# Sheet2.net
KiCad netlist of a schematic drawn in Altium Designer
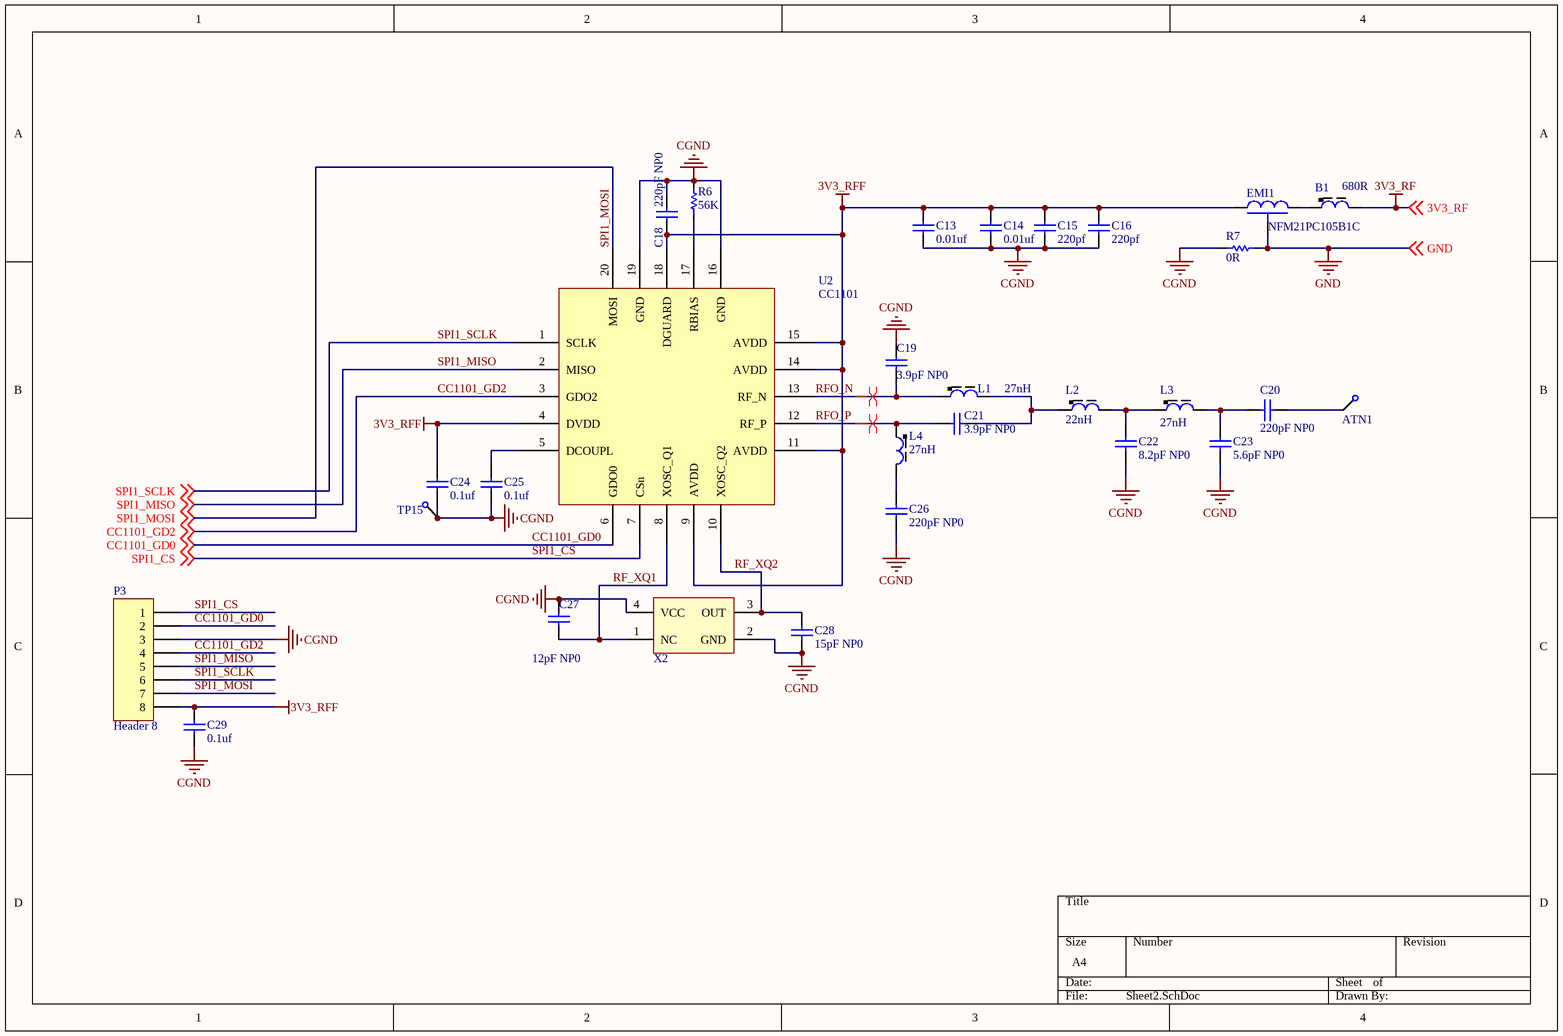
[diagram p0: Sheet2.SchDoc]

(export (version "E")
  (design (tool "Eeschema 10.0.6"))
  (components
    (comp (ref "ATN1")
      (value "TestPoint")
      (footprint "TP")
      (description "一个测试点")
      (libsource (lib "liber") (part "TestPoint"))
    )
    (comp (ref "B1") (value "680R") (footprint "L0603") (libsource (lib "liber") (part "L")))
    (comp (ref "C13")
      (value "0.01uf")
      (footprint "C0603")
      (description "Capacitor")
      (libsource (lib "liber") (part "Cap"))
    )
    (comp (ref "C14")
      (value "0.01uf")
      (footprint "C0603")
      (description "Capacitor")
      (libsource (lib "liber") (part "Cap"))
    )
    (comp (ref "C15")
      (value "220pf")
      (footprint "C0603")
      (description "Capacitor")
      (libsource (lib "liber") (part "Cap"))
    )
    (comp (ref "C16")
      (value "220pf")
      (footprint "C0603")
      (description "Capacitor")
      (libsource (lib "liber") (part "Cap"))
    )
    (comp (ref "C18")
      (value "220pF NP0")
      (footprint "C0603")
      (description "Capacitor")
      (libsource (lib "liber") (part "Cap"))
    )
    (comp (ref "C19")
      (value "3.9pF NP0")
      (footprint "C0603")
      (description "Capacitor")
      (libsource (lib "liber") (part "Cap"))
    )
    (comp (ref "C20")
      (value "220pF NP0")
      (footprint "C0603")
      (description "Capacitor")
      (libsource (lib "liber") (part "Cap"))
    )
    (comp (ref "C21")
      (value "3.9pF NP0")
      (footprint "C0603")
      (description "Capacitor")
      (libsource (lib "liber") (part "Cap"))
    )
    (comp (ref "C22")
      (value "8.2pF NP0")
      (footprint "C0603")
      (description "Capacitor")
      (libsource (lib "liber") (part "Cap"))
    )
    (comp (ref "C23")
      (value "5.6pF NP0")
      (footprint "C0603")
      (description "Capacitor")
      (libsource (lib "liber") (part "Cap"))
    )
    (comp (ref "C24")
      (value "0.1uf")
      (footprint "C0603")
      (description "Capacitor")
      (libsource (lib "liber") (part "Cap"))
    )
    (comp (ref "C25")
      (value "0.1uf")
      (footprint "C0603")
      (description "Capacitor")
      (libsource (lib "liber") (part "Cap"))
    )
    (comp (ref "C26")
      (value "220pF NP0")
      (footprint "C0603")
      (description "Capacitor")
      (libsource (lib "liber") (part "Cap"))
    )
    (comp (ref "C27")
      (value "12pF NP0")
      (footprint "C0603")
      (description "Capacitor")
      (libsource (lib "liber") (part "Cap"))
    )
    (comp (ref "C28")
      (value "15pF NP0")
      (footprint "C0603")
      (description "Capacitor")
      (libsource (lib "liber") (part "Cap"))
    )
    (comp (ref "C29")
      (value "0.1uf")
      (footprint "C0603")
      (description "Capacitor")
      (libsource (lib "liber") (part "Cap"))
    )
    (comp (ref "EMI1")
      (value "NFM21PC105B1C")
      (footprint "NFM21PC")
      (libsource (lib "liber") (part "NFM21PC105B1C"))
    )
    (comp (ref "L1")
      (value "27nH")
      (footprint "L0603")
      (description "LQG15HS27NJ02D")
      (libsource (lib "liber") (part "L"))
    )
    (comp (ref "L2") (value "22nH") (footprint "L0603") (libsource (lib "liber") (part "L")))
    (comp (ref "L3")
      (value "27nH")
      (footprint "L0603")
      (description "LQG15HS27NJ02D")
      (libsource (lib "liber") (part "L"))
    )
    (comp (ref "L4")
      (value "27nH")
      (footprint "L0603")
      (description "LQG15HS27NJ02D")
      (libsource (lib "liber") (part "L"))
    )
    (comp (ref "P3")
      (value "Header 8")
      (footprint "CC1101")
      (description "Header, 8-Pin")
      (fields (field (name "PUBLISHER") "Altium Limited"))
      (libsource (lib "Miscellaneous Connectors") (part "Header 8"))
    )
    (comp (ref "R6")
      (value "56K")
      (footprint "R0603")
      (fields (field (name "PUBLISHER") "Altium Limited"))
      (libsource (lib "liber") (part "Res"))
    )
    (comp (ref "R7")
      (value "0R")
      (footprint "R0603")
      (fields (field (name "PUBLISHER") "Altium Limited"))
      (libsource (lib "liber") (part "Res"))
    )
    (comp (ref "TP15")
      (value "TestPoint")
      (footprint "TP_0.8")
      (description "一个测试点")
      (libsource (lib "liber") (part "TestPoint"))
    )
    (comp (ref "U2")
      (value "CC1101")
      (footprint "QFN50P400X400X80_HS-21N")
      (libsource (lib "liber") (part "CC1101"))
    )
    (comp (ref "X2") (value "XTAL4") (footprint "liber:XTAL3225") (libsource (lib "liber") (part "XTAL4")))
  )
  (nets
    (net (code "1") (name "/RFO_N") (class "Default")
      (node (ref "C19") (pin "1") (pinfunction "1_1") (pintype "passive"))
      (node (ref "L1") (pin "1") (pinfunction "1_1") (pintype "passive"))
      (node (ref "U2") (pin "13") (pinfunction "RF_N_13") (pintype "passive"))
    )
    (net (code "2") (name "/RFO_P") (class "Default")
      (node (ref "C21") (pin "2") (pinfunction "2_2") (pintype "passive"))
      (node (ref "L4") (pin "1") (pinfunction "1_1") (pintype "passive"))
      (node (ref "U2") (pin "12") (pinfunction "RF_P_12") (pintype "passive"))
    )
    (net (code "3") (name "/RF_XQ1") (class "Default")
      (node (ref "C27") (pin "1") (pinfunction "1_1") (pintype "passive"))
      (node (ref "U2") (pin "8") (pinfunction "XOSC_Q1_8") (pintype "passive"))
      (node (ref "X2") (pin "1") (pinfunction "NC_1") (pintype "passive"))
    )
    (net (code "4") (name "/RF_XQ2") (class "Default")
      (node (ref "C28") (pin "2") (pinfunction "2_2") (pintype "passive"))
      (node (ref "U2") (pin "10") (pinfunction "XOSC_Q2_10") (pintype "passive"))
      (node (ref "X2") (pin "3") (pinfunction "OUT_3") (pintype "passive"))
    )
    (net (code "5") (name "3V3_RF") (class "Default")
      (node (ref "B1") (pin "2") (pinfunction "2_2") (pintype "passive"))
    )
    (net (code "6") (name "3V3_RFF") (class "Default")
      (node (ref "C13") (pin "2") (pinfunction "2_2") (pintype "passive"))
      (node (ref "C14") (pin "2") (pinfunction "2_2") (pintype "passive"))
      (node (ref "C15") (pin "2") (pinfunction "2_2") (pintype "passive"))
      (node (ref "C16") (pin "2") (pinfunction "2_2") (pintype "passive"))
      (node (ref "C18") (pin "1") (pinfunction "1_1") (pintype "passive"))
      (node (ref "C24") (pin "2") (pinfunction "2_2") (pintype "passive"))
      (node (ref "C29") (pin "2") (pinfunction "2_2") (pintype "passive"))
      (node (ref "EMI1") (pin "1") (pinfunction "1_1") (pintype "passive"))
      (node (ref "P3") (pin "8") (pinfunction "8_8") (pintype "passive"))
      (node (ref "U2") (pin "11") (pinfunction "AVDD_11") (pintype "passive"))
      (node (ref "U2") (pin "14") (pinfunction "AVDD_14") (pintype "passive"))
      (node (ref "U2") (pin "15") (pinfunction "AVDD_15") (pintype "passive"))
      (node (ref "U2") (pin "18") (pinfunction "DGUARD_18") (pintype "passive"))
      (node (ref "U2") (pin "4") (pinfunction "DVDD_4") (pintype "passive"))
      (node (ref "U2") (pin "9") (pinfunction "AVDD_9") (pintype "passive"))
    )
    (net (code "7") (name "CC1101_GD0") (class "Default")
      (node (ref "P3") (pin "2") (pinfunction "2_2") (pintype "passive"))
      (node (ref "U2") (pin "6") (pinfunction "GDO0_6") (pintype "passive"))
    )
    (net (code "8") (name "CC1101_GD2") (class "Default")
      (node (ref "P3") (pin "4") (pinfunction "4_4") (pintype "passive"))
      (node (ref "U2") (pin "3") (pinfunction "GDO2_3") (pintype "passive"))
    )
    (net (code "9") (name "CGND") (class "Default")
      (node (ref "C13") (pin "1") (pinfunction "1_1") (pintype "passive"))
      (node (ref "C14") (pin "1") (pinfunction "1_1") (pintype "passive"))
      (node (ref "C15") (pin "1") (pinfunction "1_1") (pintype "passive"))
      (node (ref "C16") (pin "1") (pinfunction "1_1") (pintype "passive"))
      (node (ref "C18") (pin "2") (pinfunction "2_2") (pintype "passive"))
      (node (ref "C19") (pin "2") (pinfunction "2_2") (pintype "passive"))
      (node (ref "C22") (pin "1") (pinfunction "1_1") (pintype "passive"))
      (node (ref "C23") (pin "1") (pinfunction "1_1") (pintype "passive"))
      (node (ref "C24") (pin "1") (pinfunction "1_1") (pintype "passive"))
      (node (ref "C25") (pin "1") (pinfunction "1_1") (pintype "passive"))
      (node (ref "C26") (pin "1") (pinfunction "1_1") (pintype "passive"))
      (node (ref "C27") (pin "2") (pinfunction "2_2") (pintype "passive"))
      (node (ref "C28") (pin "1") (pinfunction "1_1") (pintype "passive"))
      (node (ref "C29") (pin "1") (pinfunction "1_1") (pintype "passive"))
      (node (ref "P3") (pin "3") (pinfunction "3_3") (pintype "passive"))
      (node (ref "R6") (pin "2") (pinfunction "2_2") (pintype "passive"))
      (node (ref "R7") (pin "1") (pinfunction "1_1") (pintype "passive"))
      (node (ref "TP15") (pin "1") (pinfunction "1_1") (pintype "passive"))
      (node (ref "U2") (pin "16") (pinfunction "GND_16") (pintype "passive"))
      (node (ref "U2") (pin "19") (pinfunction "GND_19") (pintype "passive"))
      (node (ref "X2") (pin "2") (pinfunction "GND_2") (pintype "passive"))
      (node (ref "X2") (pin "4") (pinfunction "VCC_4") (pintype "passive"))
    )
    (net (code "10") (name "GND") (class "Default")
      (node (ref "EMI1") (pin "2") (pinfunction "2_2") (pintype "passive"))
      (node (ref "R7") (pin "2") (pinfunction "2_2") (pintype "passive"))
    )
    (net (code "11") (name "Net-(ATN1-Pad1)") (class "Default")
      (node (ref "ATN1") (pin "1") (pinfunction "1_1") (pintype "passive"))
      (node (ref "C20") (pin "1") (pinfunction "1_1") (pintype "passive"))
    )
    (net (code "12") (name "Net-(B1-Pad1)") (class "Default")
      (node (ref "B1") (pin "1") (pinfunction "1_1") (pintype "passive"))
      (node (ref "EMI1") (pin "3") (pinfunction "3_3") (pintype "passive"))
    )
    (net (code "13") (name "Net-(C20-Pad2)") (class "Default")
      (node (ref "C20") (pin "2") (pinfunction "2_2") (pintype "passive"))
      (node (ref "C23") (pin "2") (pinfunction "2_2") (pintype "passive"))
      (node (ref "L3") (pin "2") (pinfunction "2_2") (pintype "passive"))
    )
    (net (code "14") (name "Net-(C21-Pad1)") (class "Default")
      (node (ref "C21") (pin "1") (pinfunction "1_1") (pintype "passive"))
      (node (ref "L1") (pin "2") (pinfunction "2_2") (pintype "passive"))
      (node (ref "L2") (pin "1") (pinfunction "1_1") (pintype "passive"))
    )
    (net (code "15") (name "Net-(C22-Pad2)") (class "Default")
      (node (ref "C22") (pin "2") (pinfunction "2_2") (pintype "passive"))
      (node (ref "L2") (pin "2") (pinfunction "2_2") (pintype "passive"))
      (node (ref "L3") (pin "1") (pinfunction "1_1") (pintype "passive"))
    )
    (net (code "16") (name "Net-(C26-Pad2)") (class "Default")
      (node (ref "C26") (pin "2") (pinfunction "2_2") (pintype "passive"))
      (node (ref "L4") (pin "2") (pinfunction "2_2") (pintype "passive"))
    )
    (net (code "17") (name "Net-(U2-DCOUPL)") (class "Default")
      (node (ref "C25") (pin "2") (pinfunction "2_2") (pintype "passive"))
      (node (ref "U2") (pin "5") (pinfunction "DCOUPL_5") (pintype "passive"))
    )
    (net (code "18") (name "Net-(U2-RBIAS)") (class "Default")
      (node (ref "R6") (pin "1") (pinfunction "1_1") (pintype "passive"))
      (node (ref "U2") (pin "17") (pinfunction "RBIAS_17") (pintype "passive"))
    )
    (net (code "19") (name "SPI1_CS") (class "Default")
      (node (ref "P3") (pin "1") (pinfunction "1_1") (pintype "passive"))
      (node (ref "U2") (pin "7") (pinfunction "CSn_7") (pintype "passive"))
    )
    (net (code "20") (name "SPI1_MISO") (class "Default")
      (node (ref "P3") (pin "5") (pinfunction "5_5") (pintype "passive"))
      (node (ref "U2") (pin "2") (pinfunction "MISO_2") (pintype "passive"))
    )
    (net (code "21") (name "SPI1_MOSI") (class "Default")
      (node (ref "P3") (pin "7") (pinfunction "7_7") (pintype "passive"))
      (node (ref "U2") (pin "20") (pinfunction "MOSI_20") (pintype "passive"))
    )
    (net (code "22") (name "SPI1_SCLK") (class "Default")
      (node (ref "P3") (pin "6") (pinfunction "6_6") (pintype "passive"))
      (node (ref "U2") (pin "1") (pinfunction "SCLK_1") (pintype "passive"))
    )
  )
)
